# 1-Schematic_hackercard.net
KiCad netlist of a schematic drawn in EasyEDA
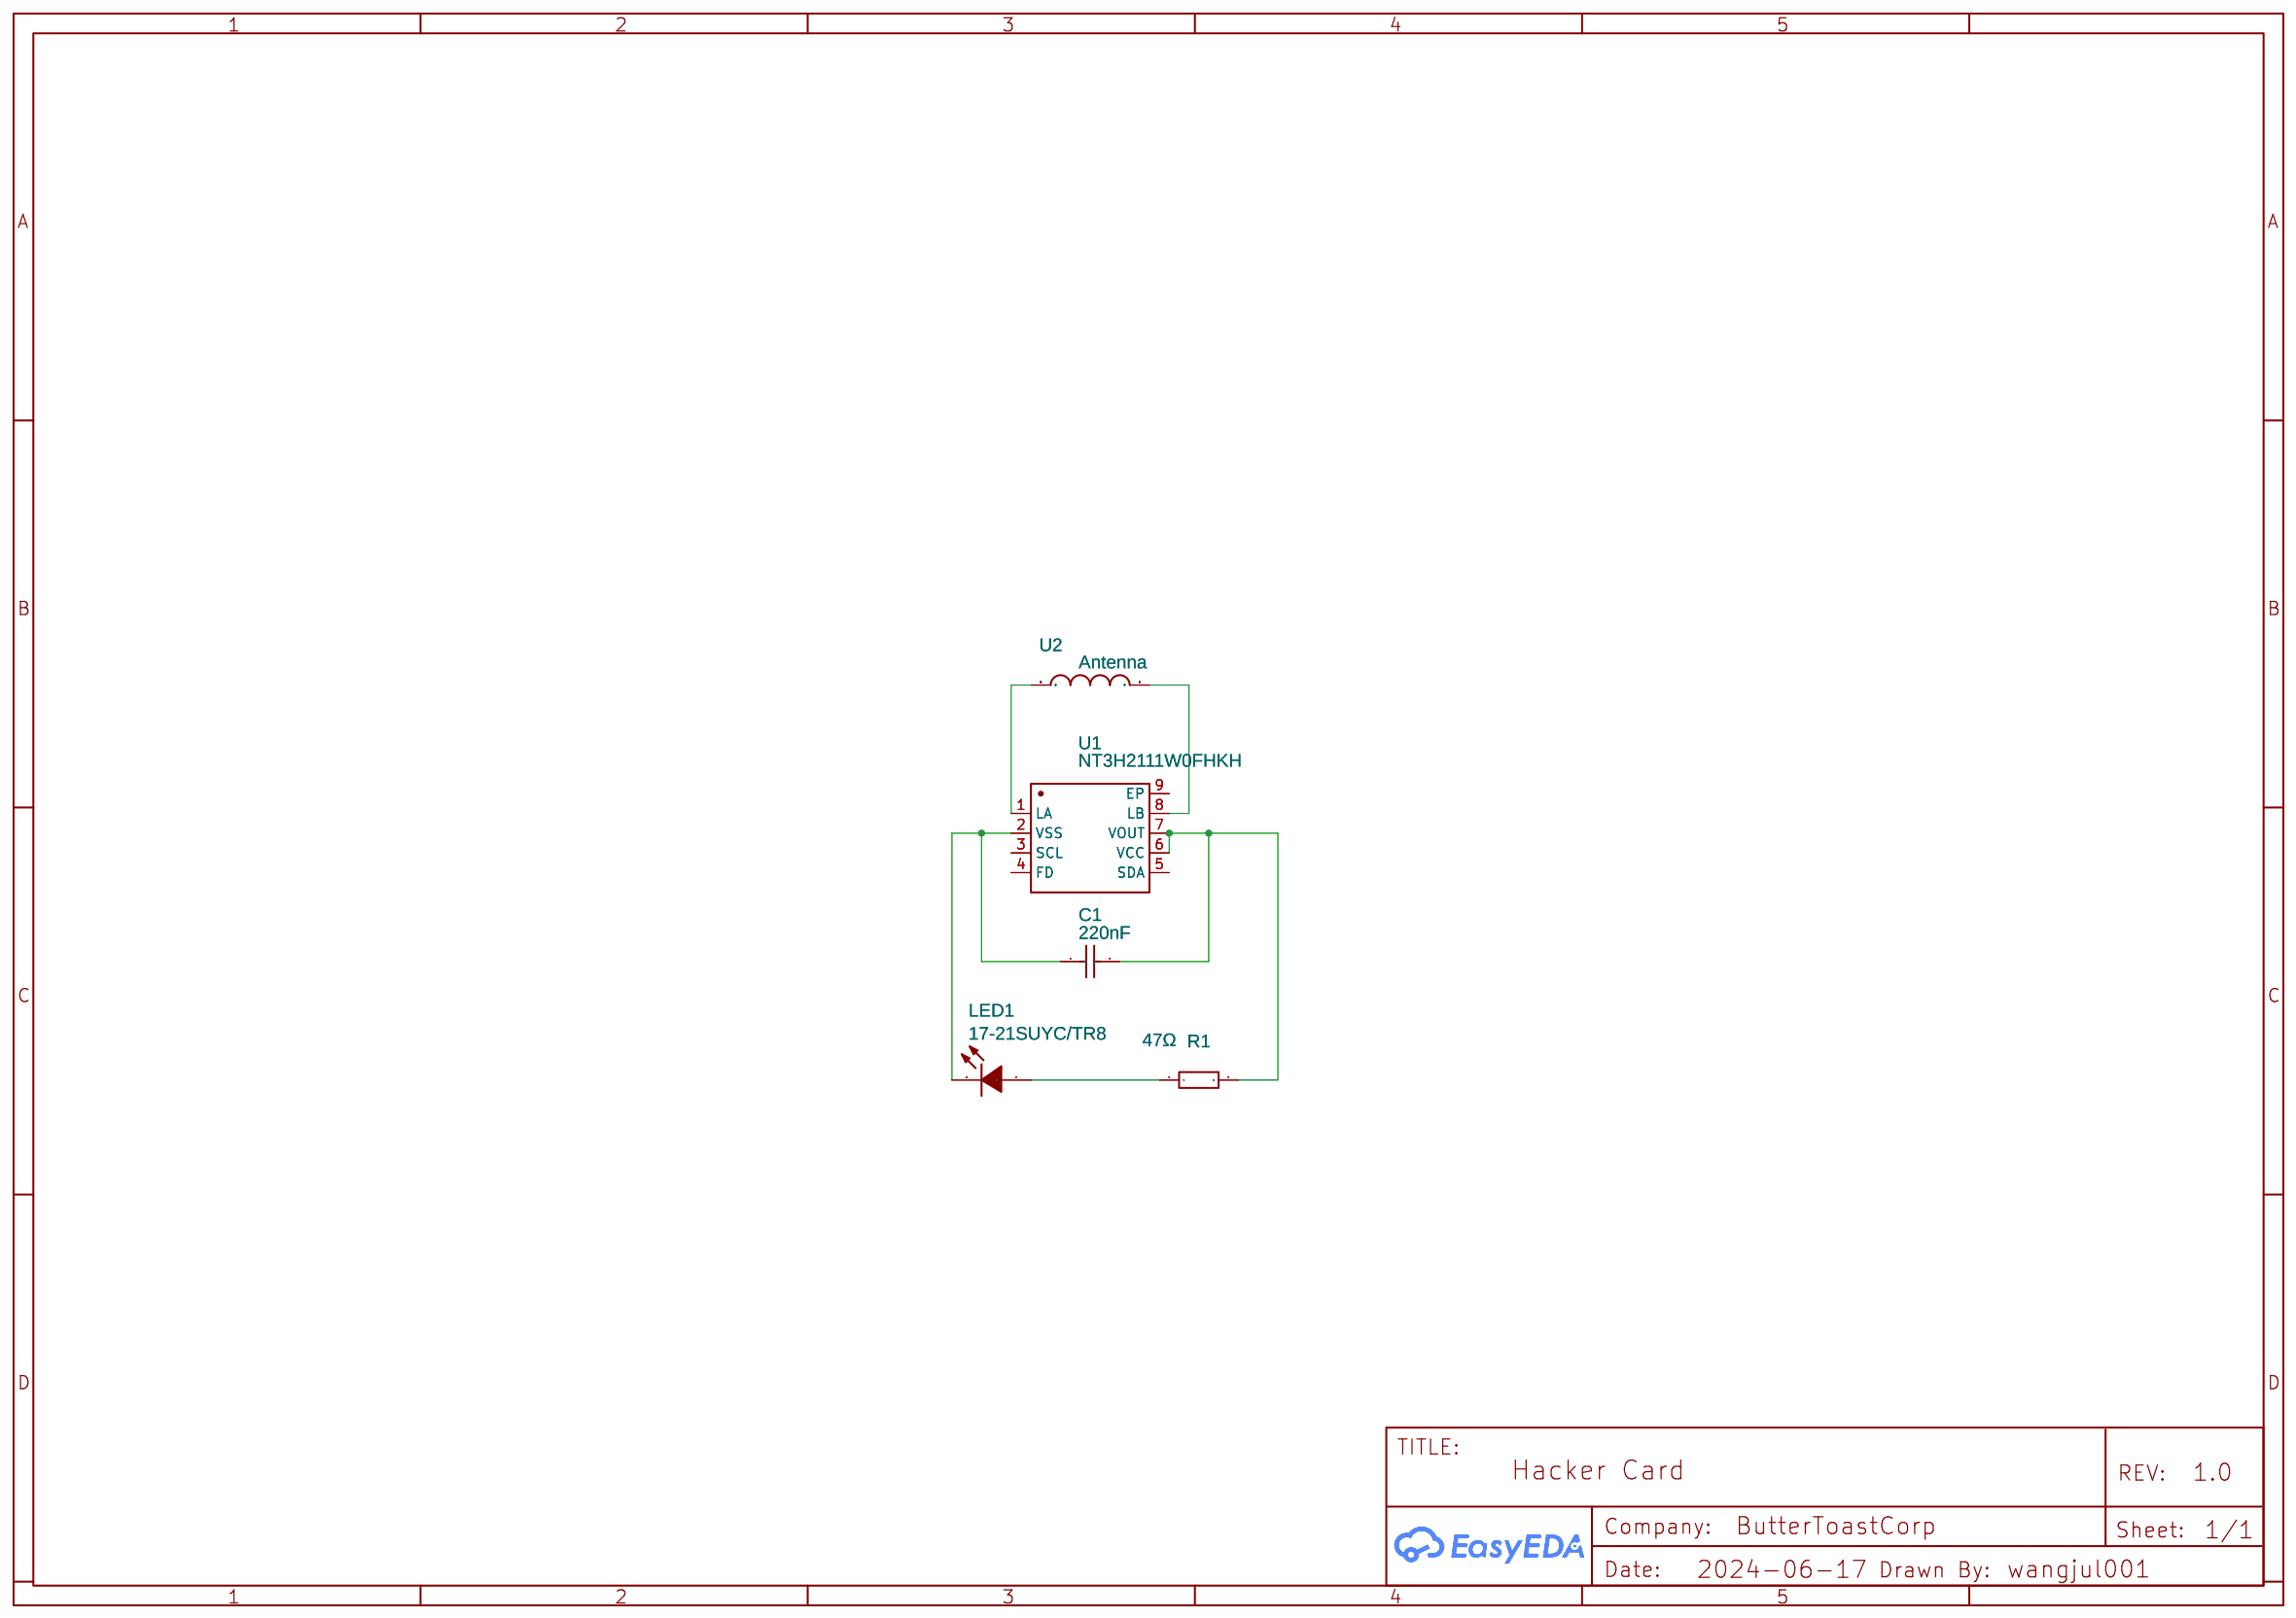
[diagram p0: schematic sheet]

(export (version "E")
  (design (tool "Eeschema 10.0.6"))
  (components
    (comp (ref "C1")
      (value "220nF")
      (fields
        (field (name "Manufacturer Part") "CL10B224KA8NNNC")
        (field (name "Manufacturer") "SAMSUNG(三星)")
      )
      (libsource (lib "") (part "CL10B224KA8NNNC"))
    )
    (comp (ref "LED1")
      (value "17-21SUYC/TR8")
      (fields (field (name "Manufacturer Part") "KT-0805黄灯") (field (name "Manufacturer") "KENTO"))
      (libsource (lib "") (part "17-21SUYC/TR8"))
    )
    (comp (ref "R1")
      (value "47Ω")
      (fields
        (field (name "Manufacturer Part") "0603WAF470JT5E")
        (field (name "Manufacturer") "UNI-ROYAL(厚声)")
      )
      (libsource (lib "") (part "0603WAF470JT5E"))
    )
    (comp (ref "U1")
      (value "NT3H2111W0FHKH")
      (fields (field (name "Manufacturer") "NXP(恩智浦)"))
      (libsource (lib "") (part "NT3H2111W0FHKH"))
    )
    (comp (ref "U2") (value "Antenna") (libsource (lib "") (part "Antenna")))
  )
  (nets
    (net (code "1") (name "Net-(LED1-+)") (class "Default")
      (node (ref "LED1") (pin "1") (pinfunction "+_1") (pintype "unspecified"))
      (node (ref "R1") (pin "1") (pinfunction "1_1") (pintype "input"))
    )
    (net (code "2") (name "Net-(LED1--)") (class "Default")
      (node (ref "C1") (pin "1") (pinfunction "1_1") (pintype "input"))
      (node (ref "LED1") (pin "2") (pinfunction "-_2") (pintype "unspecified"))
      (node (ref "U1") (pin "2") (pinfunction "VSS_2") (pintype "unspecified"))
    )
    (net (code "3") (name "Net-(U1-LA)") (class "Default")
      (node (ref "U1") (pin "1") (pinfunction "LA_1") (pintype "unspecified"))
      (node (ref "U2") (pin "P$2") (pinfunction "P$2_P$2") (pintype "unspecified"))
    )
    (net (code "4") (name "Net-(U1-LB)") (class "Default")
      (node (ref "U1") (pin "8") (pinfunction "LB_8") (pintype "unspecified"))
      (node (ref "U2") (pin "P$1") (pinfunction "P$1_P$1") (pintype "unspecified"))
    )
    (net (code "5") (name "Net-(U1-VCC)") (class "Default")
      (node (ref "C1") (pin "2") (pinfunction "2_2") (pintype "input"))
      (node (ref "R1") (pin "2") (pinfunction "2_2") (pintype "input"))
      (node (ref "U1") (pin "6") (pinfunction "VCC_6") (pintype "unspecified"))
      (node (ref "U1") (pin "7") (pinfunction "VOUT_7") (pintype "unspecified"))
    )
    (net (code "6") (name "unconnected-(U1-EP-Pad9)") (class "Default")
      (node (ref "U1") (pin "9") (pinfunction "EP_9") (pintype "unspecified"))
    )
    (net (code "7") (name "unconnected-(U1-FD-Pad4)") (class "Default")
      (node (ref "U1") (pin "4") (pinfunction "FD_4") (pintype "unspecified"))
    )
    (net (code "8") (name "unconnected-(U1-SCL-Pad3)") (class "Default")
      (node (ref "U1") (pin "3") (pinfunction "SCL_3") (pintype "unspecified"))
    )
    (net (code "9") (name "unconnected-(U1-SDA-Pad5)") (class "Default")
      (node (ref "U1") (pin "5") (pinfunction "SDA_5") (pintype "unspecified"))
    )
  )
)
